# obc_rtc.net
KiCad netlist of a schematic drawn in Altium Designer
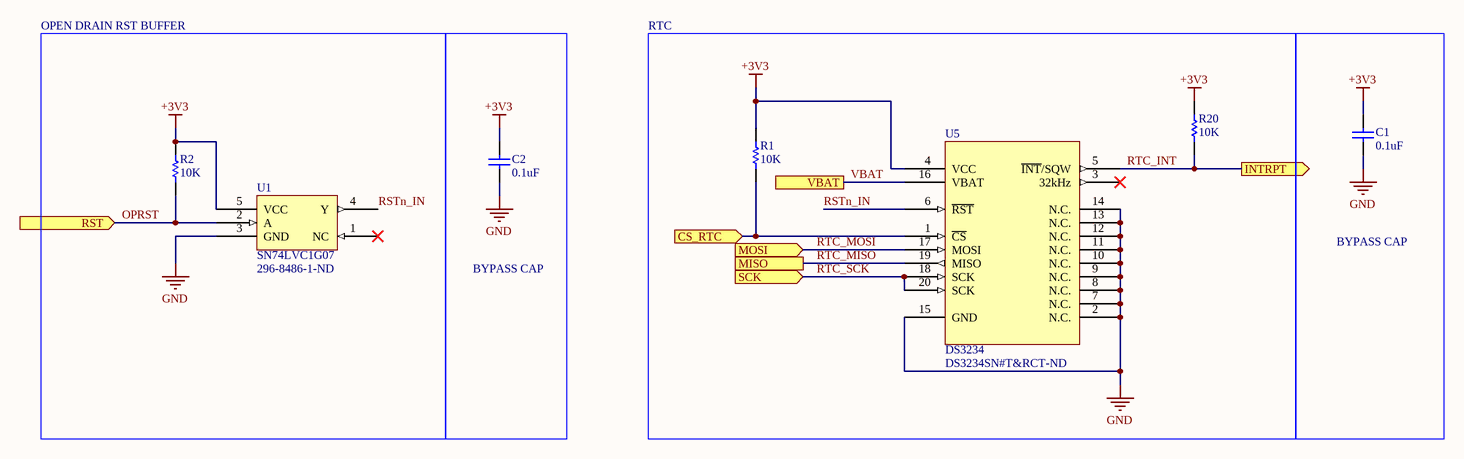
[diagram p0: obc_rtc.SchDoc]

(export (version "E")
  (design (tool "Eeschema 10.0.6"))
  (components
    (comp (ref "C1")
      (value "0.1uF")
      (footprint "CAP0603R")
      (description "0603 capacitor")
      (fields (field (name "Comment") "0603"))
      (libsource (lib "heron-general") (part "CAP0603"))
    )
    (comp (ref "C2")
      (value "0.1uF")
      (footprint "CAP0603R")
      (description "0603 capacitor")
      (fields (field (name "Comment") "0603"))
      (libsource (lib "heron-general") (part "CAP0603"))
    )
    (comp (ref "R1")
      (value "10K")
      (footprint "RES0603R")
      (description "0603 resistor")
      (fields (field (name "Comment") "0603"))
      (libsource (lib "heron-general") (part "RES0603"))
    )
    (comp (ref "R2")
      (value "10K")
      (footprint "RES0603R")
      (description "0603 resistor")
      (fields (field (name "Comment") "0603"))
      (libsource (lib "heron-general") (part "RES0603"))
    )
    (comp (ref "R20")
      (value "10K")
      (footprint "RES0603R")
      (description "0603 resistor")
      (fields (field (name "Comment") "0603"))
      (libsource (lib "heron-general") (part "RES0603"))
    )
    (comp (ref "U1")
      (value "SN74LVC1G07")
      (footprint "SOT65P210X110-5N")
      (description "Single element non-inverting open drain buffer")
      (fields (field (name "SUPPLIER PART NUMBER 1") "296-8486-1-ND"))
      (libsource (lib "ICs") (part "SN74LVC1G07"))
    )
    (comp (ref "U5")
      (value "DS3234")
      (footprint "SOIC127P1032X265-20")
      (description "SPI bus RTC with integrated crystal and SRAM")
      (fields (field (name "SUPPLIER PART NUMBER 2") "DS3234SN#T&RCT-ND"))
      (libsource (lib "heron-general") (part "DS3234"))
    )
  )
  (nets
    (net (code "1") (name "+3V3") (class "Default")
      (node (ref "C1") (pin "2") (pinfunction "2_2") (pintype "passive"))
      (node (ref "C2") (pin "2") (pinfunction "2_2") (pintype "passive"))
      (node (ref "R1") (pin "2") (pinfunction "2_2") (pintype "passive"))
      (node (ref "R2") (pin "2") (pinfunction "2_2") (pintype "passive"))
      (node (ref "R20") (pin "2") (pinfunction "2_2") (pintype "passive"))
      (node (ref "U1") (pin "5") (pinfunction "VCC_5") (pintype "power_in"))
      (node (ref "U5") (pin "4") (pinfunction "VCC_4") (pintype "power_in"))
    )
    (net (code "2") (name "/CS_RTC") (class "Default")
      (node (ref "R1") (pin "1") (pinfunction "1_1") (pintype "passive"))
      (node (ref "U5") (pin "1") (pinfunction "~{CS}_1") (pintype "input"))
    )
    (net (code "3") (name "/OPRST") (class "Default")
      (node (ref "R2") (pin "1") (pinfunction "1_1") (pintype "passive"))
      (node (ref "U1") (pin "2") (pinfunction "A_2") (pintype "input"))
    )
    (net (code "4") (name "/RSTn_IN") (class "Default")
      (node (ref "U1") (pin "4") (pinfunction "Y_4") (pintype "output"))
      (node (ref "U5") (pin "6") (pinfunction "~{RST}_6") (pintype "input"))
    )
    (net (code "5") (name "/RTC_INT") (class "Default")
      (node (ref "R20") (pin "1") (pinfunction "1_1") (pintype "passive"))
      (node (ref "U5") (pin "5") (pinfunction "~{INT}/SQW_5") (pintype "output"))
    )
    (net (code "6") (name "/RTC_MISO") (class "Default")
      (node (ref "U5") (pin "19") (pinfunction "MISO_19") (pintype "output"))
    )
    (net (code "7") (name "/RTC_MOSI") (class "Default")
      (node (ref "U5") (pin "17") (pinfunction "MOSI_17") (pintype "input"))
    )
    (net (code "8") (name "/RTC_SCK") (class "Default")
      (node (ref "U5") (pin "18") (pinfunction "SCK_18") (pintype "input"))
      (node (ref "U5") (pin "20") (pinfunction "SCK_20") (pintype "input"))
    )
    (net (code "9") (name "/VBAT") (class "Default")
      (node (ref "U5") (pin "16") (pinfunction "VBAT_16") (pintype "power_in"))
    )
    (net (code "10") (name "GND") (class "Default")
      (node (ref "C1") (pin "1") (pinfunction "1_1") (pintype "passive"))
      (node (ref "C2") (pin "1") (pinfunction "1_1") (pintype "passive"))
      (node (ref "U1") (pin "3") (pinfunction "GND_3") (pintype "power_in"))
      (node (ref "U5") (pin "10") (pinfunction "N.C._10") (pintype "passive"))
      (node (ref "U5") (pin "11") (pinfunction "N.C._11") (pintype "passive"))
      (node (ref "U5") (pin "12") (pinfunction "N.C._12") (pintype "passive"))
      (node (ref "U5") (pin "13") (pinfunction "N.C._13") (pintype "passive"))
      (node (ref "U5") (pin "14") (pinfunction "N.C._14") (pintype "passive"))
      (node (ref "U5") (pin "15") (pinfunction "GND_15") (pintype "power_in"))
      (node (ref "U5") (pin "2") (pinfunction "N.C._2") (pintype "passive"))
      (node (ref "U5") (pin "7") (pinfunction "N.C._7") (pintype "passive"))
      (node (ref "U5") (pin "8") (pinfunction "N.C._8") (pintype "passive"))
      (node (ref "U5") (pin "9") (pinfunction "N.C._9") (pintype "passive"))
    )
    (net (code "11") (name "unconnected-(U1-NC-Pad1)") (class "Default")
      (node (ref "U1") (pin "1") (pinfunction "NC_1") (pintype "input+no_connect"))
    )
    (net (code "12") (name "unconnected-(U5-32kHz-Pad3)") (class "Default")
      (node (ref "U5") (pin "3") (pinfunction "32kHz_3") (pintype "output+no_connect"))
    )
  )
)
